# MotorBreakout.net
KiCad netlist of a schematic drawn in EAGLE
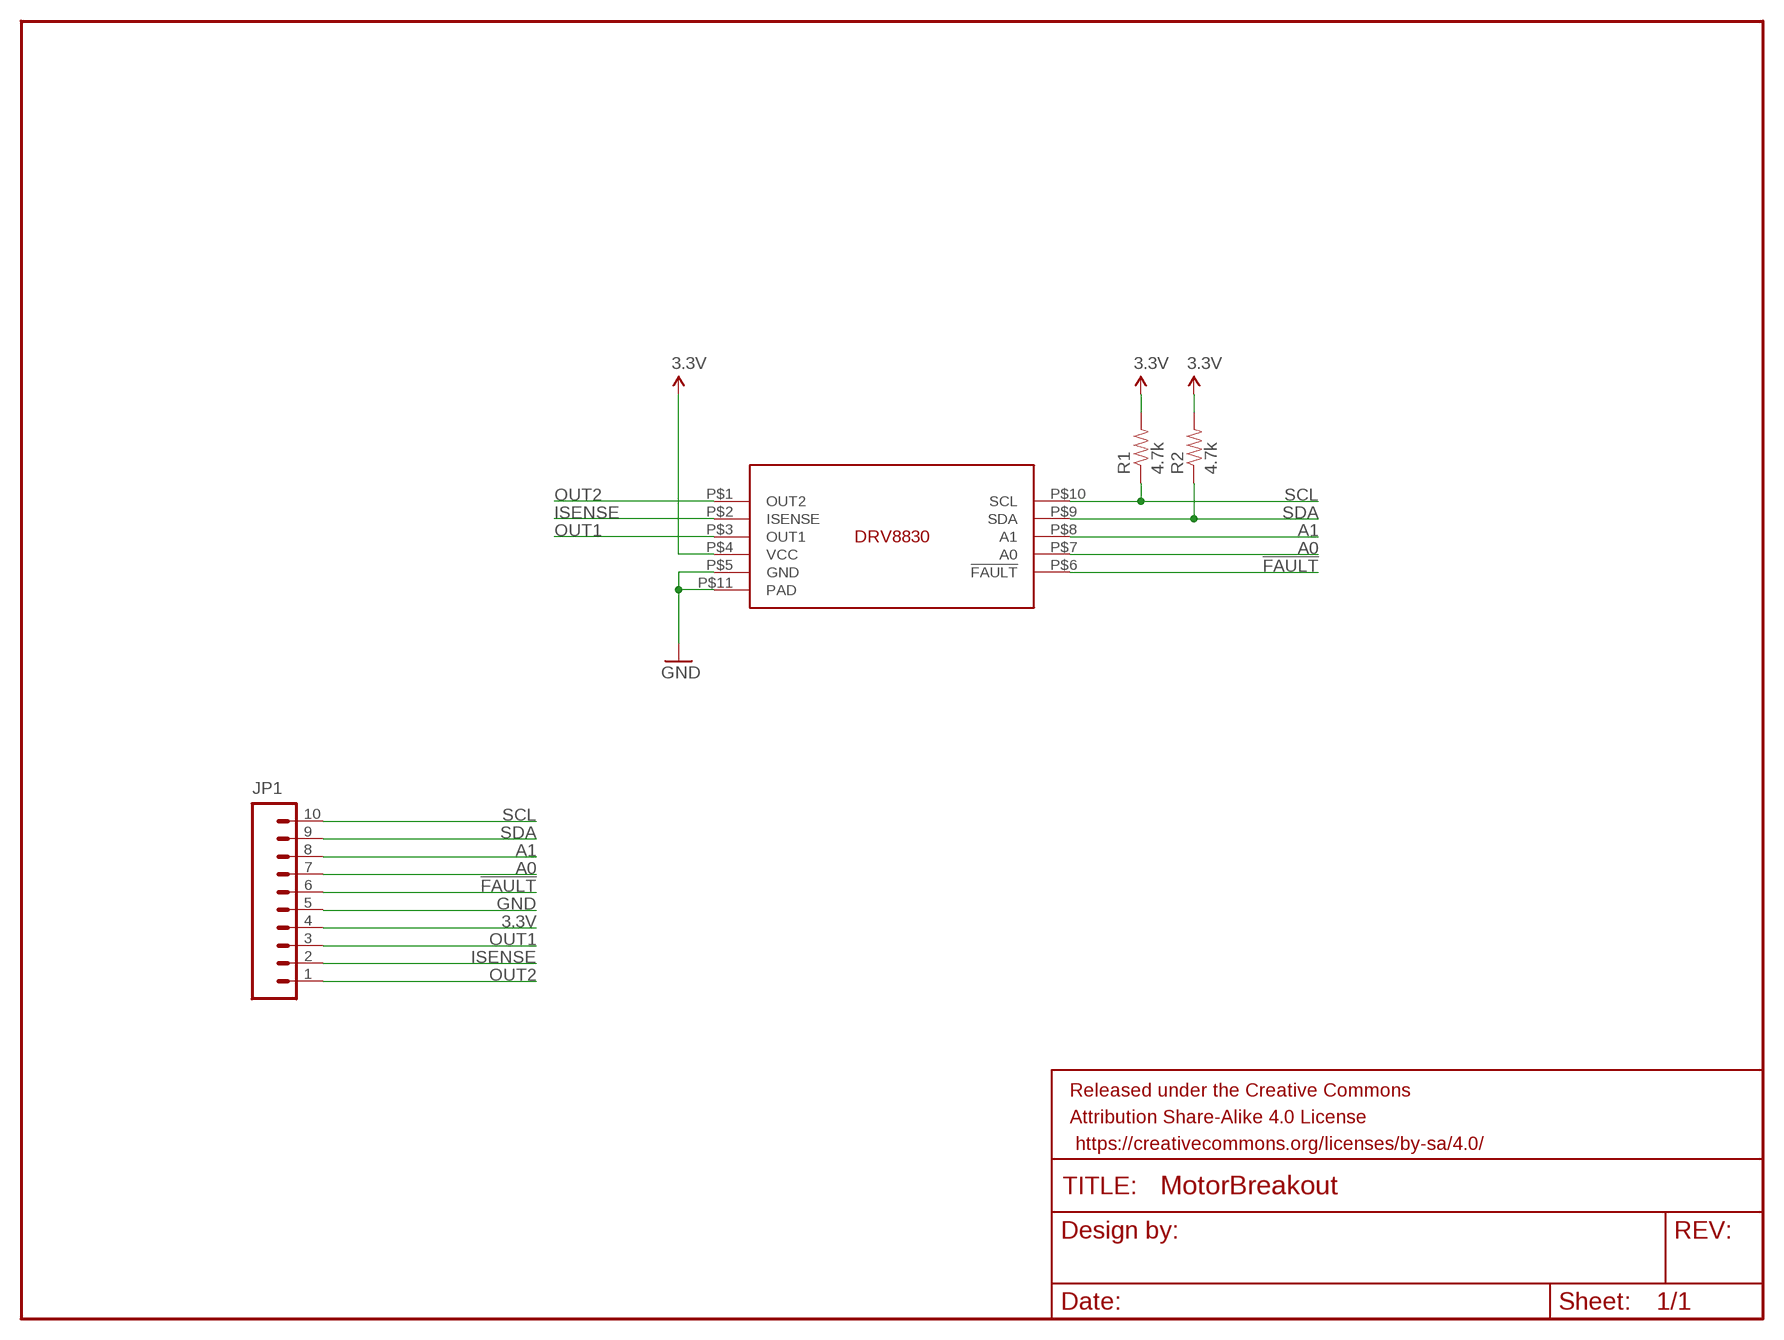
[diagram p0: schematic, sheet 1]

(export (version "E")
  (design (tool "Eeschema 10.0.6"))
  (components
    (comp (ref "FRAME1")
      (value "FRAME-LETTERNO_PACKAGE")
      (footprint "eagle-import:DUMMY")
      (fields (field (name "DESIGNER") "Nobody"))
      (libsource (lib "eagle-import") (part "FRAME-LETTERNO_PACKAGE"))
    )
    (comp (ref "JP1")
      (value "M10LOCK_LONGPADS")
      (footprint "eagle-import:1X10_LOCK_LONGPADS")
      (libsource (lib "eagle-import") (part "M10LOCK_LONGPADS"))
    )
    (comp (ref "R1")
      (value "4.7k")
      (footprint "eagle-import:0402-RES")
      (libsource (lib "eagle-import") (part "RESISTOR0402"))
    )
    (comp (ref "R2")
      (value "4.7k")
      (footprint "eagle-import:0402-RES")
      (libsource (lib "eagle-import") (part "RESISTOR0402"))
    )
    (comp (ref "U$1")
      (value "DRV8830")
      (footprint "eagle-import:DRV8830")
      (libsource (lib "eagle-import") (part "DRV8830"))
    )
  )
  (nets
    (net (code "1") (name "/A0") (class "Default")
      (node (ref "JP1") (pin "7") (pinfunction "7_7") (pintype "passive"))
      (node (ref "U$1") (pin "P$7") (pinfunction "A0_P$7") (pintype "bidirectional"))
    )
    (net (code "2") (name "/A1") (class "Default")
      (node (ref "JP1") (pin "8") (pinfunction "8_8") (pintype "passive"))
      (node (ref "U$1") (pin "P$8") (pinfunction "A1_P$8") (pintype "bidirectional"))
    )
    (net (code "3") (name "/ISENSE") (class "Default")
      (node (ref "JP1") (pin "2") (pinfunction "2_2") (pintype "passive"))
      (node (ref "U$1") (pin "P$2") (pinfunction "ISENSE_P$2") (pintype "bidirectional"))
    )
    (net (code "4") (name "/OUT1") (class "Default")
      (node (ref "JP1") (pin "3") (pinfunction "3_3") (pintype "passive"))
      (node (ref "U$1") (pin "P$3") (pinfunction "OUT1_P$3") (pintype "bidirectional"))
    )
    (net (code "5") (name "/OUT2") (class "Default")
      (node (ref "JP1") (pin "1") (pinfunction "1_1") (pintype "passive"))
      (node (ref "U$1") (pin "P$1") (pinfunction "OUT2_P$1") (pintype "bidirectional"))
    )
    (net (code "6") (name "/SCL") (class "Default")
      (node (ref "JP1") (pin "10") (pinfunction "10_10") (pintype "passive"))
      (node (ref "R1") (pin "1") (pinfunction "1_1") (pintype "passive"))
      (node (ref "U$1") (pin "P$10") (pinfunction "SCL_P$10") (pintype "bidirectional"))
    )
    (net (code "7") (name "/SDA") (class "Default")
      (node (ref "JP1") (pin "9") (pinfunction "9_9") (pintype "passive"))
      (node (ref "R2") (pin "1") (pinfunction "1_1") (pintype "passive"))
      (node (ref "U$1") (pin "P$9") (pinfunction "SDA_P$9") (pintype "bidirectional"))
    )
    (net (code "8") (name "/~{FAULT}") (class "Default")
      (node (ref "JP1") (pin "6") (pinfunction "6_6") (pintype "passive"))
      (node (ref "U$1") (pin "P$6") (pinfunction "~{FAULT}_P$6") (pintype "bidirectional"))
    )
    (net (code "9") (name "3.3V") (class "Default")
      (node (ref "JP1") (pin "4") (pinfunction "4_4") (pintype "passive"))
      (node (ref "R1") (pin "2") (pinfunction "2_2") (pintype "passive"))
      (node (ref "R2") (pin "2") (pinfunction "2_2") (pintype "passive"))
      (node (ref "U$1") (pin "P$4") (pinfunction "VCC_P$4") (pintype "bidirectional"))
    )
    (net (code "10") (name "GND") (class "Default")
      (node (ref "JP1") (pin "5") (pinfunction "5_5") (pintype "passive"))
      (node (ref "U$1") (pin "P$11") (pinfunction "PAD_P$11") (pintype "bidirectional"))
      (node (ref "U$1") (pin "P$5") (pinfunction "GND_P$5") (pintype "bidirectional"))
    )
  )
)
